# ArduinoBasic.net
KiCad netlist of a schematic drawn in EAGLE
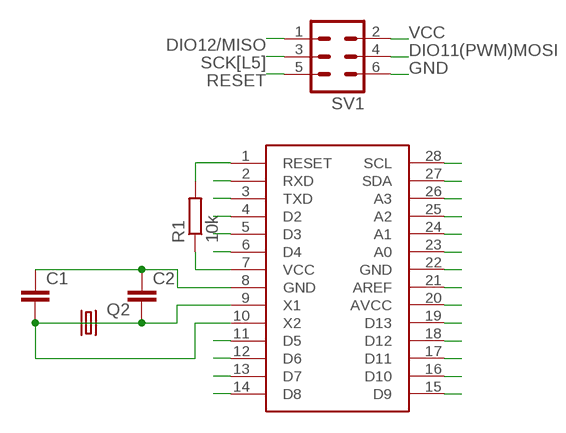
[diagram p0: schematic, sheet 1]

(export (version "E")
  (design (tool "Eeschema 10.0.6"))
  (components
    (comp (ref "C1")
      (value "C-EU025-024X044")
      (footprint "eagle-import:C025-024X044")
      (libsource (lib "eagle-import") (part "C-EU025-024X044"))
    )
    (comp (ref "C2")
      (value "C-EU025-024X044")
      (footprint "eagle-import:C025-024X044")
      (libsource (lib "eagle-import") (part "C-EU025-024X044"))
    )
    (comp (ref "Q2")
      (value "CRYSTALHC49S")
      (footprint "eagle-import:HC49_S")
      (libsource (lib "eagle-import") (part "CRYSTALHC49S"))
    )
    (comp (ref "R1")
      (value "10k")
      (footprint "eagle-import:0207_15")
      (libsource (lib "eagle-import") (part "R-EU_0207/15"))
    )
    (comp (ref "SV1")
      (value "MA03-2")
      (footprint "eagle-import:MA03-2")
      (libsource (lib "eagle-import") (part "MA03-2"))
    )
    (comp (ref "U$1")
      (value "ATMEGA328P-PU")
      (footprint "eagle-import:DIL28-3")
      (libsource (lib "eagle-import") (part "ATMEGA328P-PU"))
    )
  )
  (nets
    (net (code "1") (name "/DIO11(PWM)MOSI") (class "Default")
      (node (ref "SV1") (pin "4") (pinfunction "4_4") (pintype "passive"))
      (node (ref "U$1") (pin "17") (pinfunction "D11_17") (pintype "bidirectional"))
    )
    (net (code "2") (name "/DIO12{slash}MISO") (class "Default")
      (node (ref "SV1") (pin "1") (pinfunction "1_1") (pintype "passive"))
      (node (ref "U$1") (pin "18") (pinfunction "D12_18") (pintype "bidirectional"))
    )
    (net (code "3") (name "/GND") (class "Default")
      (node (ref "C1") (pin "1") (pinfunction "1_1") (pintype "passive"))
      (node (ref "C2") (pin "1") (pinfunction "1_1") (pintype "passive"))
      (node (ref "SV1") (pin "6") (pinfunction "6_6") (pintype "passive"))
      (node (ref "U$1") (pin "22") (pinfunction "GND_22") (pintype "bidirectional"))
      (node (ref "U$1") (pin "8") (pinfunction "GND_8") (pintype "bidirectional"))
    )
    (net (code "4") (name "/RESET") (class "Default")
      (node (ref "R1") (pin "2") (pinfunction "2_2") (pintype "passive"))
      (node (ref "SV1") (pin "5") (pinfunction "5_5") (pintype "passive"))
      (node (ref "U$1") (pin "1") (pinfunction "RESET_1") (pintype "bidirectional"))
    )
    (net (code "5") (name "/SCK[L5]") (class "Default")
      (node (ref "SV1") (pin "3") (pinfunction "3_3") (pintype "passive"))
      (node (ref "U$1") (pin "19") (pinfunction "D13_19") (pintype "bidirectional"))
    )
    (net (code "6") (name "/VCC") (class "Default")
      (node (ref "R1") (pin "1") (pinfunction "1_1") (pintype "passive"))
      (node (ref "SV1") (pin "2") (pinfunction "2_2") (pintype "passive"))
      (node (ref "U$1") (pin "20") (pinfunction "AVCC_20") (pintype "bidirectional"))
      (node (ref "U$1") (pin "7") (pinfunction "VCC_7") (pintype "bidirectional"))
    )
    (net (code "7") (name "Net-(U$1-X1)") (class "Default")
      (node (ref "C2") (pin "2") (pinfunction "2_2") (pintype "passive"))
      (node (ref "Q2") (pin "1") (pinfunction "1_1") (pintype "passive"))
      (node (ref "U$1") (pin "9") (pinfunction "X1_9") (pintype "bidirectional"))
    )
    (net (code "8") (name "Net-(U$1-X2)") (class "Default")
      (node (ref "C1") (pin "2") (pinfunction "2_2") (pintype "passive"))
      (node (ref "Q2") (pin "2") (pinfunction "2_2") (pintype "passive"))
      (node (ref "U$1") (pin "10") (pinfunction "X2_10") (pintype "bidirectional"))
    )
    (net (code "9") (name "unconnected-(U$1-A0-Pad23)") (class "Default")
      (node (ref "U$1") (pin "23") (pinfunction "A0_23") (pintype "bidirectional"))
    )
    (net (code "10") (name "unconnected-(U$1-A1-Pad24)") (class "Default")
      (node (ref "U$1") (pin "24") (pinfunction "A1_24") (pintype "bidirectional"))
    )
    (net (code "11") (name "unconnected-(U$1-A2-Pad25)") (class "Default")
      (node (ref "U$1") (pin "25") (pinfunction "A2_25") (pintype "bidirectional"))
    )
    (net (code "12") (name "unconnected-(U$1-A3-Pad26)") (class "Default")
      (node (ref "U$1") (pin "26") (pinfunction "A3_26") (pintype "bidirectional"))
    )
    (net (code "13") (name "unconnected-(U$1-AREF-Pad21)") (class "Default")
      (node (ref "U$1") (pin "21") (pinfunction "AREF_21") (pintype "bidirectional"))
    )
    (net (code "14") (name "unconnected-(U$1-D2-Pad4)") (class "Default")
      (node (ref "U$1") (pin "4") (pinfunction "D2_4") (pintype "bidirectional"))
    )
    (net (code "15") (name "unconnected-(U$1-D3-Pad5)") (class "Default")
      (node (ref "U$1") (pin "5") (pinfunction "D3_5") (pintype "bidirectional"))
    )
    (net (code "16") (name "unconnected-(U$1-D4-Pad6)") (class "Default")
      (node (ref "U$1") (pin "6") (pinfunction "D4_6") (pintype "bidirectional"))
    )
    (net (code "17") (name "unconnected-(U$1-D5-Pad11)") (class "Default")
      (node (ref "U$1") (pin "11") (pinfunction "D5_11") (pintype "bidirectional"))
    )
    (net (code "18") (name "unconnected-(U$1-D6-Pad12)") (class "Default")
      (node (ref "U$1") (pin "12") (pinfunction "D6_12") (pintype "bidirectional"))
    )
    (net (code "19") (name "unconnected-(U$1-D7-Pad13)") (class "Default")
      (node (ref "U$1") (pin "13") (pinfunction "D7_13") (pintype "bidirectional"))
    )
    (net (code "20") (name "unconnected-(U$1-D8-Pad14)") (class "Default")
      (node (ref "U$1") (pin "14") (pinfunction "D8_14") (pintype "bidirectional"))
    )
    (net (code "21") (name "unconnected-(U$1-D9-Pad15)") (class "Default")
      (node (ref "U$1") (pin "15") (pinfunction "D9_15") (pintype "bidirectional"))
    )
    (net (code "22") (name "unconnected-(U$1-D10-Pad16)") (class "Default")
      (node (ref "U$1") (pin "16") (pinfunction "D10_16") (pintype "bidirectional"))
    )
    (net (code "23") (name "unconnected-(U$1-RXD-Pad2)") (class "Default")
      (node (ref "U$1") (pin "2") (pinfunction "RXD_2") (pintype "bidirectional"))
    )
    (net (code "24") (name "unconnected-(U$1-SCL-Pad28)") (class "Default")
      (node (ref "U$1") (pin "28") (pinfunction "SCL_28") (pintype "bidirectional"))
    )
    (net (code "25") (name "unconnected-(U$1-SDA-Pad27)") (class "Default")
      (node (ref "U$1") (pin "27") (pinfunction "SDA_27") (pintype "bidirectional"))
    )
    (net (code "26") (name "unconnected-(U$1-TXD-Pad3)") (class "Default")
      (node (ref "U$1") (pin "3") (pinfunction "TXD_3") (pintype "bidirectional"))
    )
  )
)
